# lis2dh12_breakout.net
KiCad netlist of a schematic drawn in EAGLE
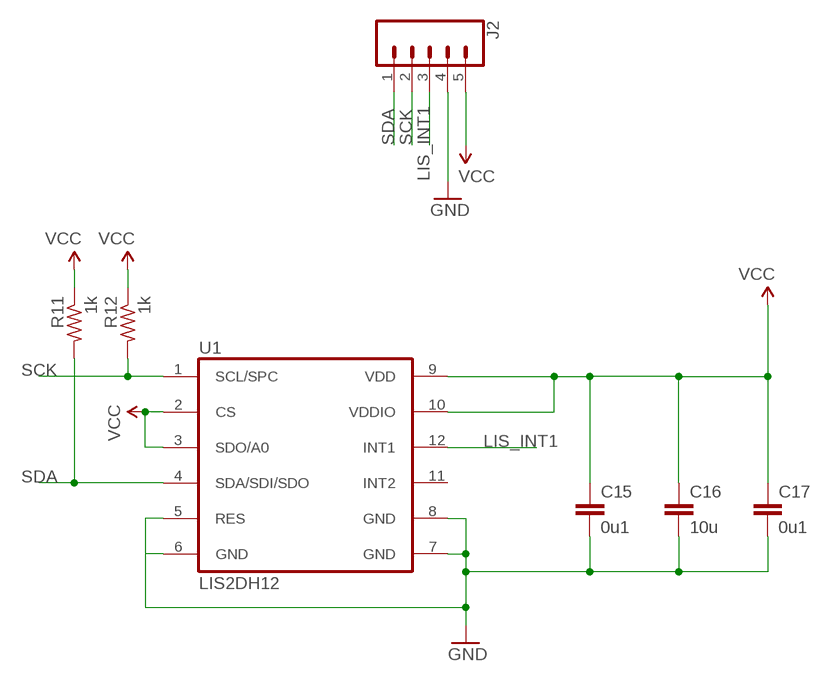
[diagram p0: schematic, sheet 1]

(export (version "E")
  (design (tool "Eeschema 10.0.6"))
  (components
    (comp (ref "C15")
      (value "0u1")
      (footprint "eagle-import:C0603")
      (libsource (lib "eagle-import") (part "C-EUC0603"))
    )
    (comp (ref "C16")
      (value "10u")
      (footprint "eagle-import:C0603")
      (libsource (lib "eagle-import") (part "C-EUC0603"))
    )
    (comp (ref "C17")
      (value "0u1")
      (footprint "eagle-import:C0603")
      (libsource (lib "eagle-import") (part "C-EUC0603"))
    )
    (comp (ref "J2")
      (value "CONN_05NO_SILK")
      (footprint "eagle-import:1X05_NO_SILK")
      (libsource (lib "eagle-import") (part "CONN_05NO_SILK"))
    )
    (comp (ref "R11")
      (value "1k")
      (footprint "eagle-import:R0603")
      (libsource (lib "eagle-import") (part "R-US_R0603"))
    )
    (comp (ref "R12")
      (value "1k")
      (footprint "eagle-import:R0603")
      (libsource (lib "eagle-import") (part "R-US_R0603"))
    )
    (comp (ref "U1")
      (value "LIS2DH12")
      (footprint "eagle-import:LGA12")
      (libsource (lib "eagle-import") (part "LIS2DH12"))
    )
  )
  (nets
    (net (code "1") (name "/LIS_INT1") (class "Default")
      (node (ref "J2") (pin "3") (pinfunction "3_3") (pintype "passive"))
      (node (ref "U1") (pin "12") (pinfunction "INT1_12") (pintype "output"))
    )
    (net (code "2") (name "/SCK") (class "Default")
      (node (ref "J2") (pin "2") (pinfunction "2_2") (pintype "passive"))
      (node (ref "R12") (pin "2") (pinfunction "2_2") (pintype "passive"))
      (node (ref "U1") (pin "1") (pinfunction "SCL/SPC_1") (pintype "bidirectional"))
    )
    (net (code "3") (name "/SDA") (class "Default")
      (node (ref "J2") (pin "1") (pinfunction "1_1") (pintype "passive"))
      (node (ref "R11") (pin "2") (pinfunction "2_2") (pintype "passive"))
      (node (ref "U1") (pin "4") (pinfunction "SDA/SDI/SDO_4") (pintype "bidirectional"))
    )
    (net (code "4") (name "GND") (class "Default")
      (node (ref "C15") (pin "2") (pinfunction "2_2") (pintype "passive"))
      (node (ref "C16") (pin "2") (pinfunction "2_2") (pintype "passive"))
      (node (ref "C17") (pin "2") (pinfunction "2_2") (pintype "passive"))
      (node (ref "J2") (pin "4") (pinfunction "4_4") (pintype "passive"))
      (node (ref "U1") (pin "5") (pinfunction "RES_5") (pintype "input"))
      (node (ref "U1") (pin "6") (pinfunction "GND_6") (pintype "power_in"))
      (node (ref "U1") (pin "7") (pinfunction "GND_7") (pintype "power_in"))
      (node (ref "U1") (pin "8") (pinfunction "GND_8") (pintype "bidirectional"))
    )
    (net (code "5") (name "VCC") (class "Default")
      (node (ref "C15") (pin "1") (pinfunction "1_1") (pintype "passive"))
      (node (ref "C16") (pin "1") (pinfunction "1_1") (pintype "passive"))
      (node (ref "C17") (pin "1") (pinfunction "1_1") (pintype "passive"))
      (node (ref "J2") (pin "5") (pinfunction "5_5") (pintype "passive"))
      (node (ref "R11") (pin "1") (pinfunction "1_1") (pintype "passive"))
      (node (ref "R12") (pin "1") (pinfunction "1_1") (pintype "passive"))
      (node (ref "U1") (pin "10") (pinfunction "VDDIO_10") (pintype "power_in"))
      (node (ref "U1") (pin "2") (pinfunction "CS_2") (pintype "bidirectional"))
      (node (ref "U1") (pin "3") (pinfunction "SDO/A0_3") (pintype "bidirectional"))
      (node (ref "U1") (pin "9") (pinfunction "VDD_9") (pintype "power_in"))
    )
    (net (code "6") (name "unconnected-(U1-INT2-Pad11)") (class "Default")
      (node (ref "U1") (pin "11") (pinfunction "INT2_11") (pintype "output"))
    )
  )
)
